# lab1_kochurin_usb_rs485.net
KiCad netlist of a schematic drawn in Altium Designer
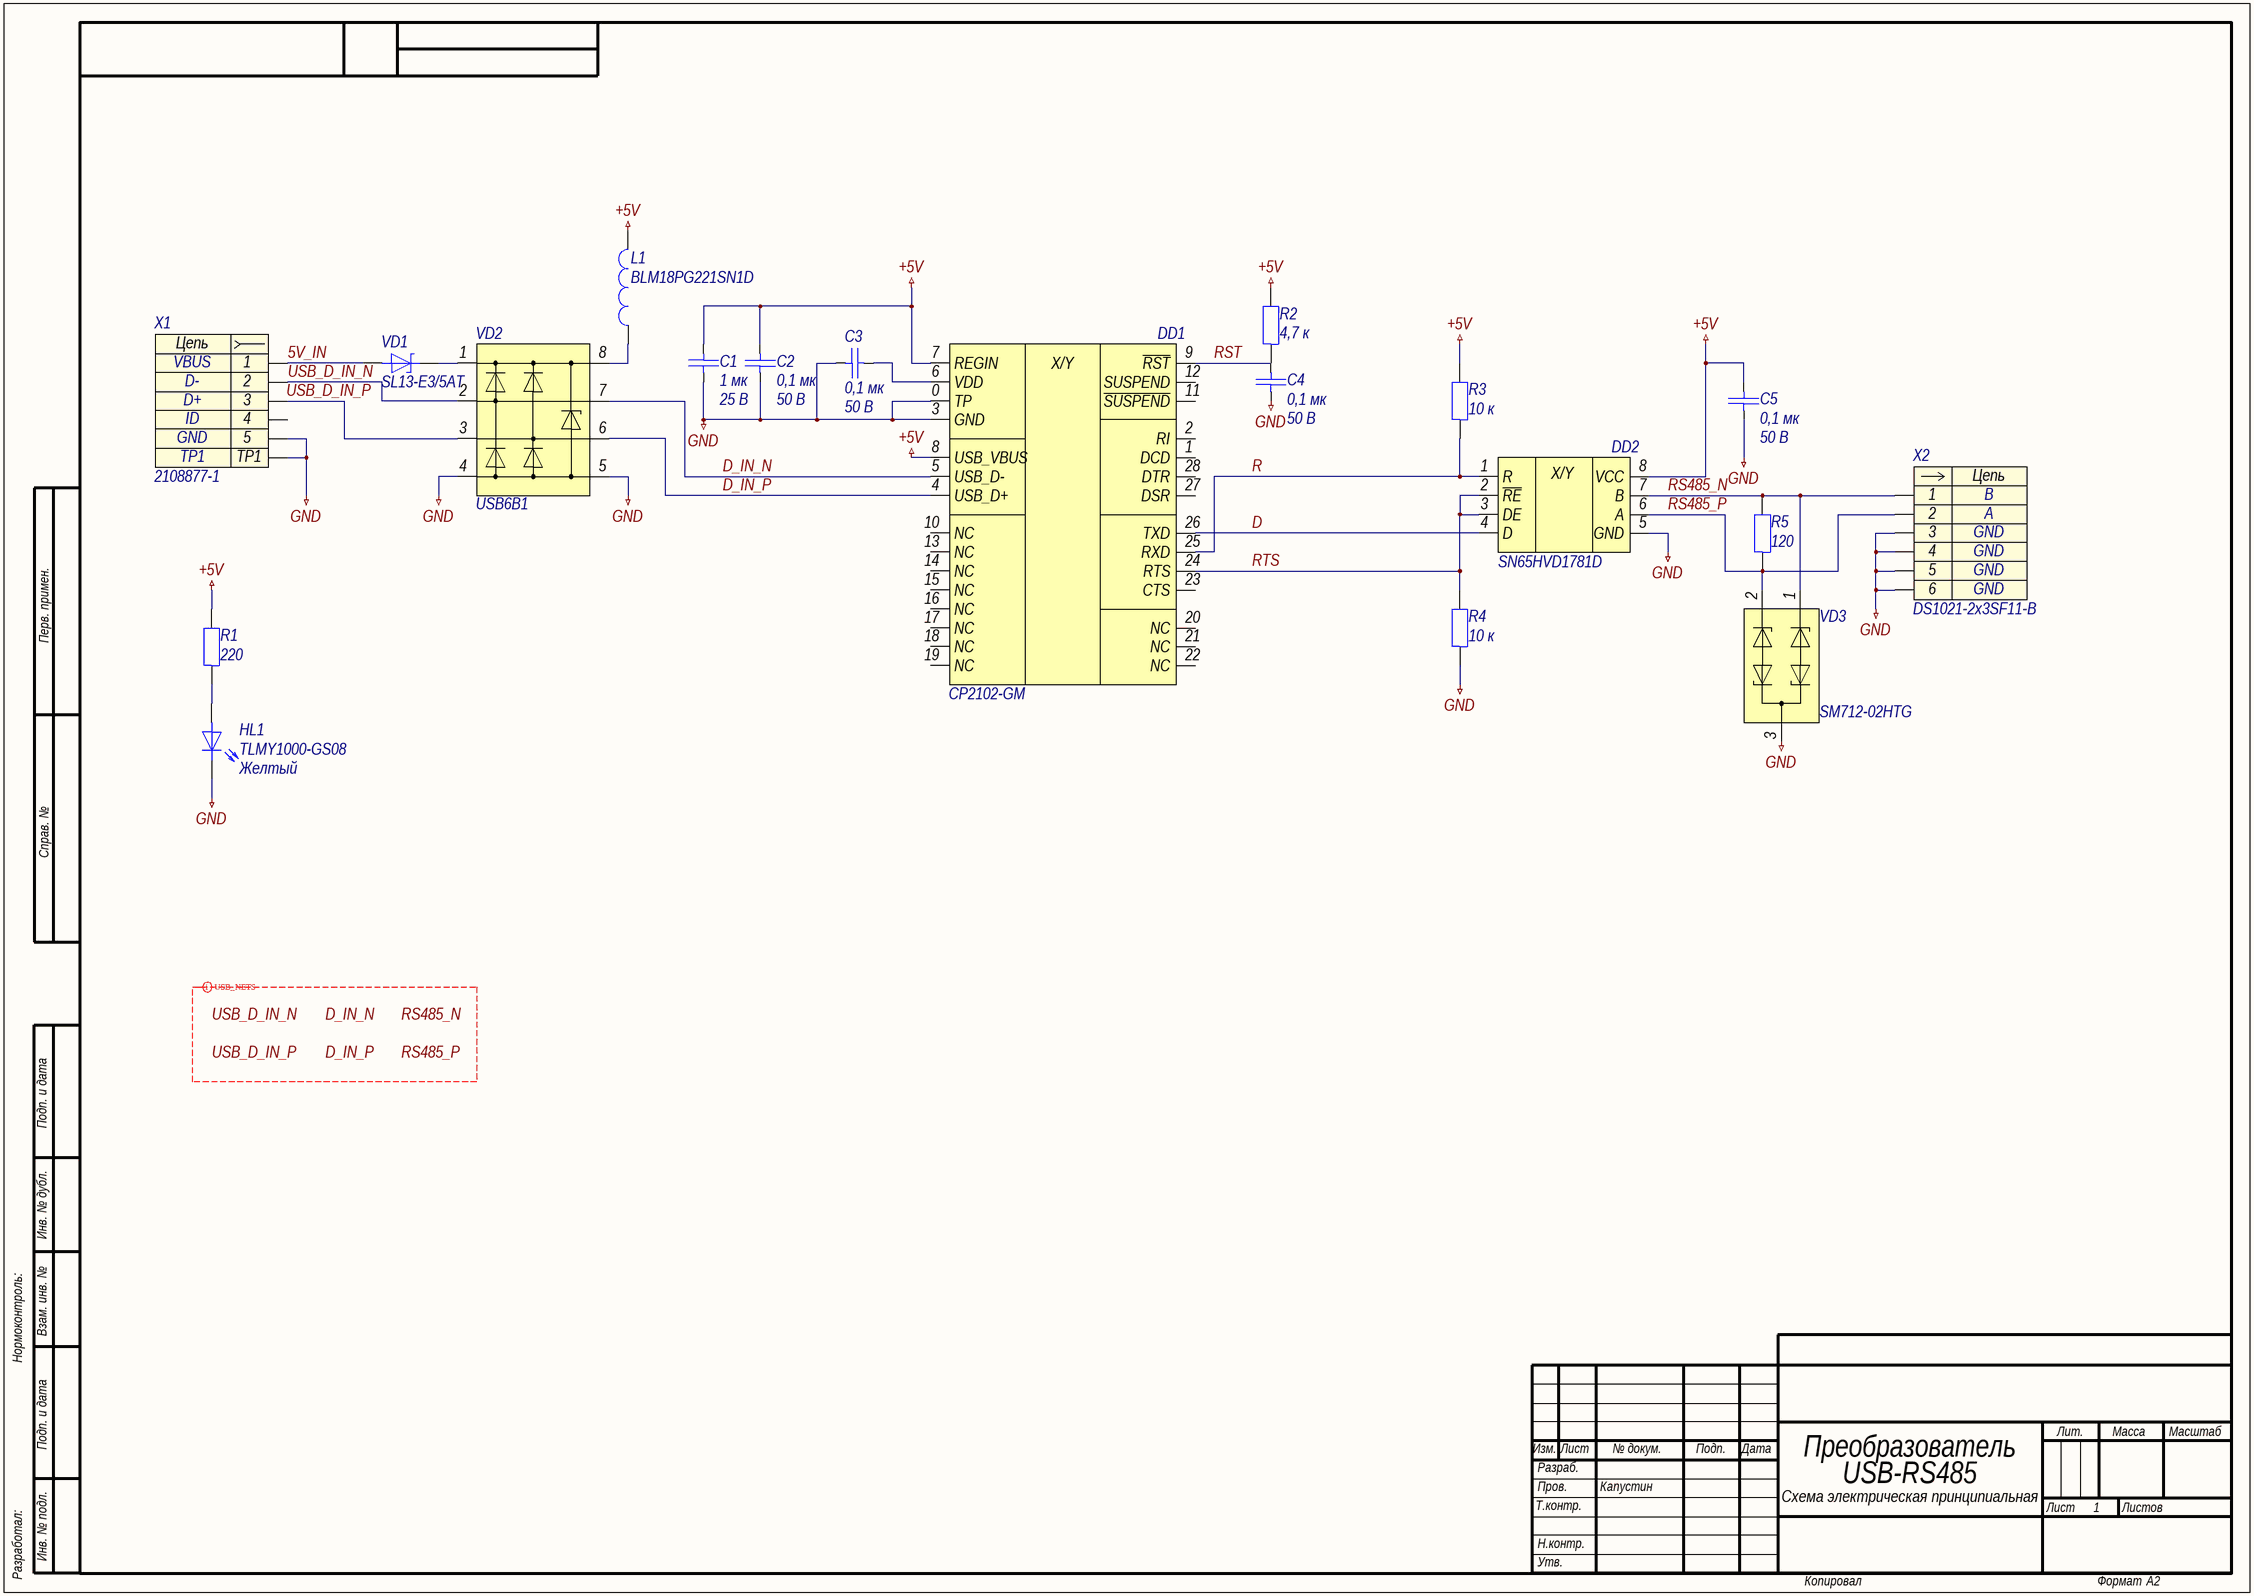
[diagram p0: lab1_kochurin_usb_rs485.SchDoc]

(export (version "E")
  (design (tool "Eeschema 10.0.6"))
  (components
    (comp (ref "C1")
      (value "1 мк")
      (footprint "C0603")
      (description "=Описание")
      (fields (field (name "НАПРЯЖЕНИЕ") "25 В"))
      (libsource (lib "Database_Students") (part "C-NONPOLAR"))
    )
    (comp (ref "C2")
      (value "0,1 мк")
      (footprint "C0603")
      (description "=Описание")
      (fields (field (name "НАПРЯЖЕНИЕ") "50 В"))
      (libsource (lib "Database_Students") (part "C-NONPOLAR"))
    )
    (comp (ref "C3")
      (value "0,1 мк")
      (footprint "C0603")
      (description "=Описание")
      (fields (field (name "НАПРЯЖЕНИЕ") "50 В"))
      (libsource (lib "Database_Students") (part "C-NONPOLAR"))
    )
    (comp (ref "C4")
      (value "0,1 мк")
      (footprint "C0603")
      (description "=Описание")
      (fields (field (name "НАПРЯЖЕНИЕ") "50 В"))
      (libsource (lib "Database_Students") (part "C-NONPOLAR"))
    )
    (comp (ref "C5")
      (value "0,1 мк")
      (footprint "C0603")
      (description "=Описание")
      (fields (field (name "НАПРЯЖЕНИЕ") "50 В"))
      (libsource (lib "Database_Students") (part "C-NONPOLAR"))
    )
    (comp (ref "DD1")
      (value "CP2102-GM")
      (footprint "QFN-28-500X500X90")
      (description "=Описание")
      (libsource (lib "Database_Students") (part "CP2102-GM"))
    )
    (comp (ref "DD2")
      (value "SN65HVD1781D")
      (footprint "SOIC-8")
      (description "=Описание")
      (libsource (lib "Database_Students") (part "SN65HVD1781D"))
    )
    (comp (ref "HL1")
      (value "TLMY1000-GS08")
      (footprint "HL0603")
      (description "=Описание")
      (fields (field (name "COLOUR") "Желтый"))
      (libsource (lib "Database_Students") (part "LED-COMMON"))
    )
    (comp (ref "L1")
      (value "BLM18PG221SN1D")
      (footprint "BLM-2-0603")
      (description "=Описание")
      (libsource (lib "Database_Students") (part "FERRITE-BEAD"))
    )
    (comp (ref "R1")
      (value "220")
      (footprint "R0603")
      (description "=Описание")
      (libsource (lib "Database_Students") (part "R-COMMON"))
    )
    (comp (ref "R2")
      (value "4,7 к")
      (footprint "R0603")
      (description "=Описание")
      (libsource (lib "Database_Students") (part "R-COMMON"))
    )
    (comp (ref "R3")
      (value "10 к")
      (footprint "R0603")
      (description "=Описание")
      (libsource (lib "Database_Students") (part "R-COMMON"))
    )
    (comp (ref "R4")
      (value "10 к")
      (footprint "R0603")
      (description "=Описание")
      (libsource (lib "Database_Students") (part "R-COMMON"))
    )
    (comp (ref "R5")
      (value "120")
      (footprint "R0603")
      (description "=Описание")
      (libsource (lib "Database_Students") (part "R-COMMON"))
    )
    (comp (ref "VD1")
      (value "SL13-E3/5AT")
      (footprint "DO-214AC")
      (description "=Описание")
      (libsource (lib "Database_Students") (part "DIODE-SCHOTTKY"))
    )
    (comp (ref "VD2")
      (value "USB6B1")
      (footprint "SOIC-8")
      (description "=Описание")
      (libsource (lib "Database_Students") (part "USB6B1"))
    )
    (comp (ref "VD3")
      (value "SM712-02HTG")
      (footprint "SOT23-3")
      (description "=Описание")
      (libsource (lib "Database_Students") (part "SM712-02HTG"))
    )
    (comp (ref "X1")
      (value "2108877-1")
      (footprint "2108877-1")
      (description "=Описание")
      (libsource (lib "Database_Students") (part "HEADER-5-TP1-SCT"))
    )
    (comp (ref "X2")
      (value "DS1021-2x3SF11-B")
      (footprint "DS1021-2X3SF11-B")
      (description "=Описание")
      (libsource (lib "Database_Students") (part "HEADER-6-PLG"))
    )
  )
  (nets
    (net (code "1") (name "+5V") (class "Default")
      (node (ref "C1") (pin "2") (pinfunction "2_2") (pintype "passive"))
      (node (ref "C2") (pin "1") (pinfunction "1_1") (pintype "passive"))
      (node (ref "C5") (pin "1") (pinfunction "1_1") (pintype "passive"))
      (node (ref "DD1") (pin "7") (pinfunction "REGIN_7") (pintype "passive"))
      (node (ref "DD1") (pin "8") (pinfunction "USB_VBUS_8") (pintype "passive"))
      (node (ref "DD2") (pin "8") (pinfunction "VCC_8") (pintype "passive"))
      (node (ref "L1") (pin "2") (pinfunction "2_2") (pintype "passive"))
      (node (ref "R1") (pin "2") (pinfunction "2_2") (pintype "passive"))
      (node (ref "R2") (pin "2") (pinfunction "2_2") (pintype "passive"))
      (node (ref "R3") (pin "2") (pinfunction "2_2") (pintype "passive"))
    )
    (net (code "2") (name "/5V_IN") (class "Default")
      (node (ref "VD1") (pin "2") (pinfunction "2_2") (pintype "passive"))
      (node (ref "X1") (pin "1") (pinfunction "1_1") (pintype "passive"))
    )
    (net (code "3") (name "/D") (class "Default")
      (node (ref "DD1") (pin "26") (pinfunction "TXD_26") (pintype "passive"))
      (node (ref "DD2") (pin "4") (pinfunction "D_4") (pintype "passive"))
    )
    (net (code "4") (name "/D_IN_N") (class "Default")
      (node (ref "DD1") (pin "5") (pinfunction "USB_D-_5") (pintype "passive"))
      (node (ref "VD2") (pin "7") (pinfunction "7_7") (pintype "passive"))
    )
    (net (code "5") (name "/D_IN_P") (class "Default")
      (node (ref "DD1") (pin "4") (pinfunction "USB_D+_4") (pintype "passive"))
      (node (ref "VD2") (pin "6") (pinfunction "6_6") (pintype "passive"))
    )
    (net (code "6") (name "/R") (class "Default")
      (node (ref "DD1") (pin "25") (pinfunction "RXD_25") (pintype "passive"))
      (node (ref "DD2") (pin "1") (pinfunction "R_1") (pintype "passive"))
      (node (ref "R3") (pin "1") (pinfunction "1_1") (pintype "passive"))
    )
    (net (code "7") (name "/RS485_N") (class "Default")
      (node (ref "DD2") (pin "7") (pinfunction "B_7") (pintype "passive"))
      (node (ref "R5") (pin "2") (pinfunction "2_2") (pintype "passive"))
      (node (ref "VD3") (pin "1") (pinfunction "1_1") (pintype "passive"))
      (node (ref "X2") (pin "1") (pinfunction "1_1") (pintype "passive"))
    )
    (net (code "8") (name "/RS485_P") (class "Default")
      (node (ref "DD2") (pin "6") (pinfunction "A_6") (pintype "passive"))
      (node (ref "R5") (pin "1") (pinfunction "1_1") (pintype "passive"))
      (node (ref "VD3") (pin "2") (pinfunction "2_2") (pintype "passive"))
      (node (ref "X2") (pin "2") (pinfunction "2_2") (pintype "passive"))
    )
    (net (code "9") (name "/RST") (class "Default")
      (node (ref "C4") (pin "1") (pinfunction "1_1") (pintype "passive"))
      (node (ref "DD1") (pin "9") (pinfunction "~{RST}_9") (pintype "passive"))
      (node (ref "R2") (pin "1") (pinfunction "1_1") (pintype "passive"))
    )
    (net (code "10") (name "/RTS") (class "Default")
      (node (ref "DD1") (pin "24") (pinfunction "RTS_24") (pintype "passive"))
      (node (ref "DD2") (pin "2") (pinfunction "~{RE}_2") (pintype "passive"))
      (node (ref "DD2") (pin "3") (pinfunction "DE_3") (pintype "passive"))
      (node (ref "R4") (pin "2") (pinfunction "2_2") (pintype "passive"))
    )
    (net (code "11") (name "/USB_D_IN_N") (class "Default")
      (node (ref "VD2") (pin "2") (pinfunction "2_2") (pintype "passive"))
      (node (ref "X1") (pin "2") (pinfunction "2_2") (pintype "passive"))
    )
    (net (code "13") (name "GND") (class "Default")
      (node (ref "C1") (pin "1") (pinfunction "1_1") (pintype "passive"))
      (node (ref "C2") (pin "2") (pinfunction "2_2") (pintype "passive"))
      (node (ref "C3") (pin "2") (pinfunction "2_2") (pintype "passive"))
      (node (ref "C4") (pin "2") (pinfunction "2_2") (pintype "passive"))
      (node (ref "C5") (pin "2") (pinfunction "2_2") (pintype "passive"))
      (node (ref "DD1") (pin "0") (pinfunction "TP_0") (pintype "passive"))
      (node (ref "DD1") (pin "3") (pinfunction "GND_3") (pintype "passive"))
      (node (ref "DD2") (pin "5") (pinfunction "GND_5") (pintype "passive"))
      (node (ref "HL1") (pin "1") (pinfunction "1_1") (pintype "passive"))
      (node (ref "R4") (pin "1") (pinfunction "1_1") (pintype "passive"))
      (node (ref "VD2") (pin "4") (pinfunction "4_4") (pintype "passive"))
      (node (ref "VD2") (pin "5") (pinfunction "5_5") (pintype "passive"))
      (node (ref "VD3") (pin "3") (pinfunction "3_3") (pintype "passive"))
      (node (ref "X1") (pin "5") (pinfunction "5_5") (pintype "passive"))
      (node (ref "X1") (pin "TP1") (pinfunction "TP1_TP1") (pintype "passive"))
      (node (ref "X2") (pin "3") (pinfunction "3_3") (pintype "passive"))
      (node (ref "X2") (pin "4") (pinfunction "4_4") (pintype "passive"))
      (node (ref "X2") (pin "5") (pinfunction "5_5") (pintype "passive"))
      (node (ref "X2") (pin "6") (pinfunction "6_6") (pintype "passive"))
    )
    (net (code "14") (name "Net-(DD1-VDD)") (class "Default")
      (node (ref "C3") (pin "1") (pinfunction "1_1") (pintype "passive"))
      (node (ref "DD1") (pin "6") (pinfunction "VDD_6") (pintype "passive"))
    )
    (net (code "15") (name "Net-(HL1-Pad2)") (class "Default")
      (node (ref "HL1") (pin "2") (pinfunction "2_2") (pintype "passive"))
      (node (ref "R1") (pin "1") (pinfunction "1_1") (pintype "passive"))
    )
    (net (code "16") (name "Net-(L1-Pad1)") (class "Default")
      (node (ref "L1") (pin "1") (pinfunction "1_1") (pintype "passive"))
      (node (ref "VD2") (pin "8") (pinfunction "8_8") (pintype "passive"))
    )
    (net (code "17") (name "Net-(VD1-Pad1)") (class "Default")
      (node (ref "VD1") (pin "1") (pinfunction "1_1") (pintype "passive"))
      (node (ref "VD2") (pin "1") (pinfunction "1_1") (pintype "passive"))
    )
    (net (code "18") (name "Net-(VD2-Pad3)") (class "Default")
      (node (ref "VD2") (pin "3") (pinfunction "3_3") (pintype "passive"))
      (node (ref "X1") (pin "3") (pinfunction "3_3") (pintype "passive"))
    )
    (net (code "19") (name "unconnected-(DD1-CTS-Pad23)") (class "Default")
      (node (ref "DD1") (pin "23") (pinfunction "CTS_23") (pintype "passive"))
    )
    (net (code "20") (name "unconnected-(DD1-DCD-Pad1)") (class "Default")
      (node (ref "DD1") (pin "1") (pinfunction "DCD_1") (pintype "passive"))
    )
    (net (code "21") (name "unconnected-(DD1-DSR-Pad27)") (class "Default")
      (node (ref "DD1") (pin "27") (pinfunction "DSR_27") (pintype "passive"))
    )
    (net (code "22") (name "unconnected-(DD1-DTR-Pad28)") (class "Default")
      (node (ref "DD1") (pin "28") (pinfunction "DTR_28") (pintype "passive"))
    )
    (net (code "23") (name "unconnected-(DD1-NC-Pad10)") (class "Default")
      (node (ref "DD1") (pin "10") (pinfunction "NC_10") (pintype "passive"))
    )
    (net (code "24") (name "unconnected-(DD1-NC-Pad13)") (class "Default")
      (node (ref "DD1") (pin "13") (pinfunction "NC_13") (pintype "passive"))
    )
    (net (code "25") (name "unconnected-(DD1-NC-Pad14)") (class "Default")
      (node (ref "DD1") (pin "14") (pinfunction "NC_14") (pintype "passive"))
    )
    (net (code "26") (name "unconnected-(DD1-NC-Pad15)") (class "Default")
      (node (ref "DD1") (pin "15") (pinfunction "NC_15") (pintype "passive"))
    )
    (net (code "27") (name "unconnected-(DD1-NC-Pad16)") (class "Default")
      (node (ref "DD1") (pin "16") (pinfunction "NC_16") (pintype "passive"))
    )
    (net (code "28") (name "unconnected-(DD1-NC-Pad17)") (class "Default")
      (node (ref "DD1") (pin "17") (pinfunction "NC_17") (pintype "passive"))
    )
    (net (code "29") (name "unconnected-(DD1-NC-Pad18)") (class "Default")
      (node (ref "DD1") (pin "18") (pinfunction "NC_18") (pintype "passive"))
    )
    (net (code "30") (name "unconnected-(DD1-NC-Pad19)") (class "Default")
      (node (ref "DD1") (pin "19") (pinfunction "NC_19") (pintype "passive"))
    )
    (net (code "31") (name "unconnected-(DD1-NC-Pad20)") (class "Default")
      (node (ref "DD1") (pin "20") (pinfunction "NC_20") (pintype "passive"))
    )
    (net (code "32") (name "unconnected-(DD1-NC-Pad21)") (class "Default")
      (node (ref "DD1") (pin "21") (pinfunction "NC_21") (pintype "passive"))
    )
    (net (code "33") (name "unconnected-(DD1-NC-Pad22)") (class "Default")
      (node (ref "DD1") (pin "22") (pinfunction "NC_22") (pintype "passive"))
    )
    (net (code "34") (name "unconnected-(DD1-RI-Pad2)") (class "Default")
      (node (ref "DD1") (pin "2") (pinfunction "RI_2") (pintype "passive"))
    )
    (net (code "35") (name "unconnected-(DD1-SUSPEND-Pad12)") (class "Default")
      (node (ref "DD1") (pin "12") (pinfunction "SUSPEND_12") (pintype "passive"))
    )
    (net (code "36") (name "unconnected-(DD1-~{SUSPEND}-Pad11)") (class "Default")
      (node (ref "DD1") (pin "11") (pinfunction "~{SUSPEND}_11") (pintype "passive"))
    )
    (net (code "37") (name "unconnected-(X1-Pad4)") (class "Default")
      (node (ref "X1") (pin "4") (pinfunction "4_4") (pintype "passive"))
    )
  )
)
